# BHOnOfreDevBoard.net
KiCad netlist of a schematic drawn in EAGLE
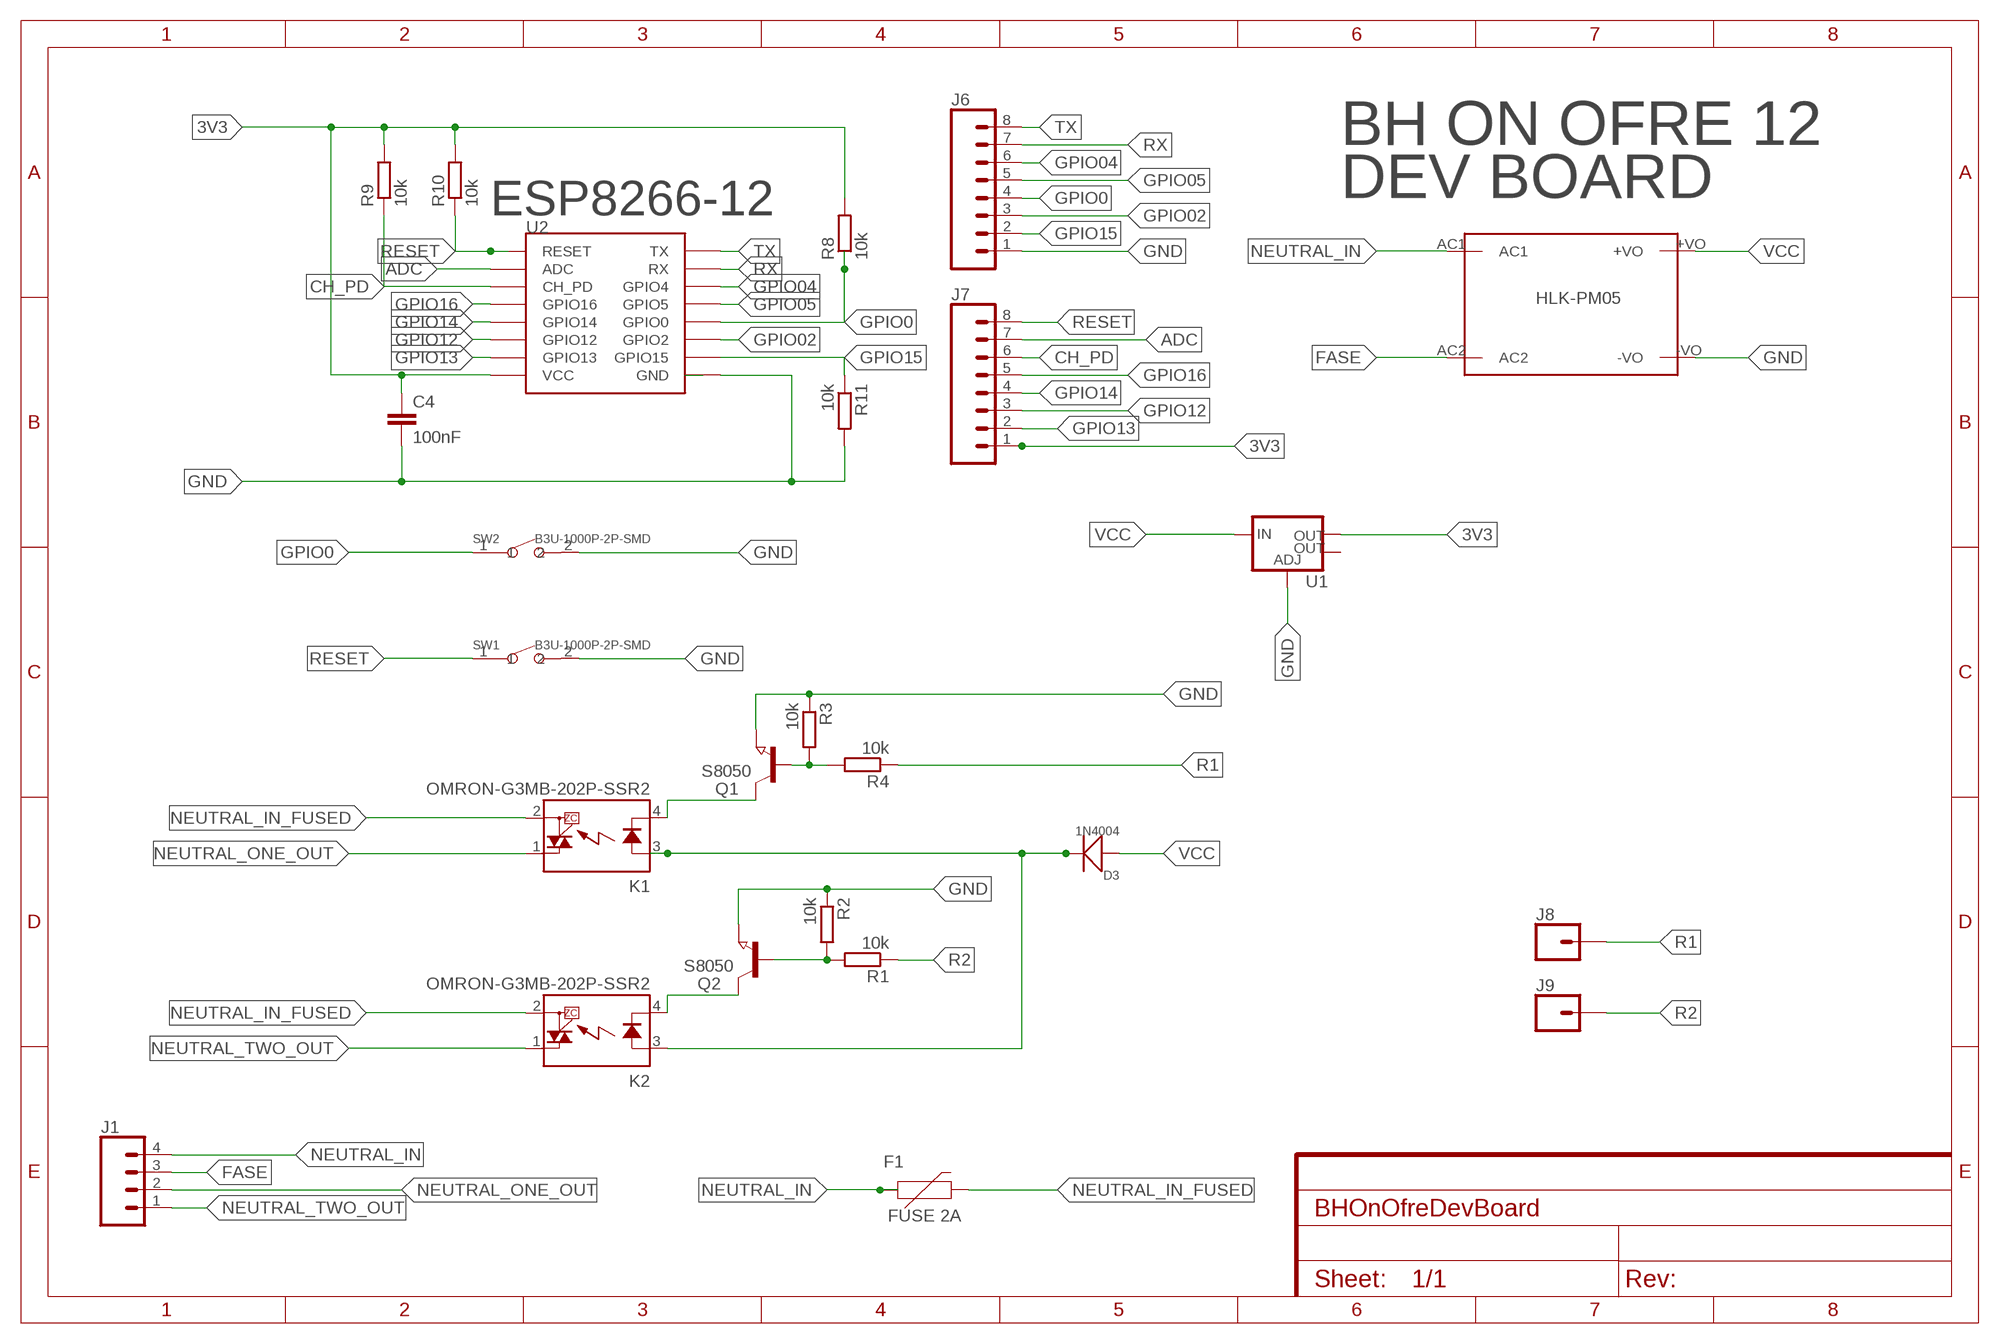
[diagram p0: schematic, sheet 1]

(export (version "E")
  (design (tool "Eeschema 10.0.6"))
  (components
    (comp (ref "C4")
      (value "100nF")
      (footprint "eagle-import:0603")
      (libsource (lib "eagle-import") (part "10NF-0603-50V-10%"))
    )
    (comp (ref "D3")
      (value "1N4004")
      (footprint "eagle-import:DO-214AC")
      (fields (field (name "MPN") "1N4007"))
      (libsource (lib "eagle-import") (part "DIODE-GEN-PURPOSE-1KV-1A(DO-214AC)"))
    )
    (comp (ref "F1")
      (value "FUSE 2A")
      (footprint "eagle-import:PTH")
      (libsource (lib "eagle-import") (part "PPTC_PTH"))
    )
    (comp (ref "J1")
      (value "CONN_04SCREW")
      (footprint "eagle-import:SCREWTERMINAL-3.5MM-4")
      (libsource (lib "eagle-import") (part "CONN_04SCREW"))
    )
    (comp (ref "J6")
      (value "CONN_08\"")
      (footprint "eagle-import:1X08")
      (libsource (lib "eagle-import") (part "CONN_08{dblquote}"))
    )
    (comp (ref "J7")
      (value "CONN_08\"")
      (footprint "eagle-import:1X08")
      (libsource (lib "eagle-import") (part "CONN_08{dblquote}"))
    )
    (comp (ref "J8")
      (value "CONN_01")
      (footprint "eagle-import:1X01")
      (libsource (lib "eagle-import") (part "CONN_01"))
    )
    (comp (ref "J9")
      (value "CONN_01")
      (footprint "eagle-import:1X01")
      (libsource (lib "eagle-import") (part "CONN_01"))
    )
    (comp (ref "K1")
      (value "OMRON-G3MB-202P-SSR2")
      (footprint "eagle-import:OMRON-G3MB-202P-SSR")
      (fields (field (name "MPN") "S202S02F"))
      (libsource (lib "eagle-import") (part "OMRON-G3MB-202P-SSR2"))
    )
    (comp (ref "K2")
      (value "OMRON-G3MB-202P-SSR2")
      (footprint "eagle-import:OMRON-G3MB-202P-SSR")
      (fields (field (name "MPN") "S202S02F"))
      (libsource (lib "eagle-import") (part "OMRON-G3MB-202P-SSR2"))
    )
    (comp (ref "Q1")
      (value "S8050")
      (footprint "eagle-import:SOT23")
      (libsource (lib "eagle-import") (part "NPN-TRANSISTOR_SOT23"))
    )
    (comp (ref "Q2")
      (value "S8050")
      (footprint "eagle-import:SOT23")
      (libsource (lib "eagle-import") (part "NPN-TRANSISTOR_SOT23"))
    )
    (comp (ref "R1")
      (value "10k")
      (footprint "eagle-import:R0603")
      (libsource (lib "eagle-import") (part "R-EU_R0603"))
    )
    (comp (ref "R2")
      (value "10k")
      (footprint "eagle-import:R0603")
      (libsource (lib "eagle-import") (part "R-EU_R0603"))
    )
    (comp (ref "R3")
      (value "10k")
      (footprint "eagle-import:R0603")
      (libsource (lib "eagle-import") (part "R-EU_R0603"))
    )
    (comp (ref "R4")
      (value "10k")
      (footprint "eagle-import:R0603")
      (libsource (lib "eagle-import") (part "R-EU_R0603"))
    )
    (comp (ref "R8")
      (value "10k")
      (footprint "eagle-import:R0603")
      (libsource (lib "eagle-import") (part "R-EU_R0603"))
    )
    (comp (ref "R9")
      (value "10k")
      (footprint "eagle-import:R0603")
      (libsource (lib "eagle-import") (part "R-EU_R0603"))
    )
    (comp (ref "R10")
      (value "10k")
      (footprint "eagle-import:R0603")
      (libsource (lib "eagle-import") (part "R-EU_R0603"))
    )
    (comp (ref "R11")
      (value "10k")
      (footprint "eagle-import:R0603")
      (libsource (lib "eagle-import") (part "R-EU_R0603"))
    )
    (comp (ref "SW1")
      (value "B3U-1000P-2P-SMD")
      (footprint "eagle-import:SW2-2.6-3.0X2.5X1.2+0.4MM")
      (libsource (lib "eagle-import") (part "SMD-BUTTON(2P-3.0X2.5X1.2+0.4MM)-B3U-1000P-2P-SMD"))
    )
    (comp (ref "SW2")
      (value "B3U-1000P-2P-SMD")
      (footprint "eagle-import:SW2-2.6-3.0X2.5X1.2+0.4MM")
      (libsource (lib "eagle-import") (part "SMD-BUTTON(2P-3.0X2.5X1.2+0.4MM)-B3U-1000P-2P-SMD"))
    )
    (comp (ref "U$2")
      (value "HLK-PM03")
      (footprint "eagle-import:HLK-PM03")
      (libsource (lib "eagle-import") (part "HLK-PM03"))
    )
    (comp (ref "U1")
      (value "V_REG_LM1117SOT223")
      (footprint "eagle-import:SOT223")
      (libsource (lib "eagle-import") (part "V_REG_LM1117SOT223"))
    )
    (comp (ref "U2")
      (value "ESP12SMD")
      (footprint "eagle-import:ESP12-SMD")
      (libsource (lib "eagle-import") (part "ESP12SMD"))
    )
  )
  (nets
    (net (code "1") (name "3V3") (class "Default")
      (node (ref "C4") (pin "1") (pinfunction "1_1") (pintype "passive"))
      (node (ref "J7") (pin "1") (pinfunction "1_1") (pintype "passive"))
      (node (ref "R10") (pin "2") (pinfunction "2_2") (pintype "passive"))
      (node (ref "R8") (pin "2") (pinfunction "2_2") (pintype "passive"))
      (node (ref "R9") (pin "2") (pinfunction "2_2") (pintype "passive"))
      (node (ref "U1") (pin "2") (pinfunction "OUT_2") (pintype "output"))
      (node (ref "U2") (pin "VCC") (pinfunction "VCC_VCC") (pintype "bidirectional"))
    )
    (net (code "2") (name "ADC") (class "Default")
      (node (ref "J7") (pin "7") (pinfunction "7_7") (pintype "passive"))
      (node (ref "U2") (pin "ADC") (pinfunction "ADC_ADC") (pintype "bidirectional"))
    )
    (net (code "3") (name "CH_PD") (class "Default")
      (node (ref "J7") (pin "6") (pinfunction "6_6") (pintype "passive"))
      (node (ref "R9") (pin "1") (pinfunction "1_1") (pintype "passive"))
      (node (ref "U2") (pin "CH_PD") (pinfunction "CH_PD_CH_PD") (pintype "bidirectional"))
    )
    (net (code "4") (name "FASE") (class "Default")
      (node (ref "J1") (pin "3") (pinfunction "3_3") (pintype "passive"))
      (node (ref "U$2") (pin "AC2") (pinfunction "AC2_AC2") (pintype "bidirectional"))
    )
    (net (code "5") (name "GND") (class "Default")
      (node (ref "C4") (pin "2") (pinfunction "2_2") (pintype "passive"))
      (node (ref "J6") (pin "1") (pinfunction "1_1") (pintype "passive"))
      (node (ref "Q1") (pin "2") (pinfunction "E_2") (pintype "passive"))
      (node (ref "Q2") (pin "2") (pinfunction "E_2") (pintype "passive"))
      (node (ref "R11") (pin "2") (pinfunction "2_2") (pintype "passive"))
      (node (ref "R2") (pin "1") (pinfunction "1_1") (pintype "passive"))
      (node (ref "R3") (pin "1") (pinfunction "1_1") (pintype "passive"))
      (node (ref "SW1") (pin "2") (pinfunction "2_2") (pintype "bidirectional"))
      (node (ref "SW2") (pin "2") (pinfunction "2_2") (pintype "bidirectional"))
      (node (ref "U$2") (pin "-VO") (pinfunction "-VO_-VO") (pintype "bidirectional"))
      (node (ref "U1") (pin "1") (pinfunction "ADJ_1") (pintype "input"))
      (node (ref "U2") (pin "GND") (pinfunction "GND_GND") (pintype "bidirectional"))
    )
    (net (code "6") (name "GPIO0") (class "Default")
      (node (ref "J6") (pin "4") (pinfunction "4_4") (pintype "passive"))
      (node (ref "R8") (pin "1") (pinfunction "1_1") (pintype "passive"))
      (node (ref "SW2") (pin "1") (pinfunction "1_1") (pintype "bidirectional"))
      (node (ref "U2") (pin "GPIO0") (pinfunction "GPIO0_GPIO0") (pintype "bidirectional"))
    )
    (net (code "7") (name "GPIO02") (class "Default")
      (node (ref "J6") (pin "3") (pinfunction "3_3") (pintype "passive"))
      (node (ref "U2") (pin "GPIO2") (pinfunction "GPIO2_GPIO2") (pintype "bidirectional"))
    )
    (net (code "8") (name "GPIO04") (class "Default")
      (node (ref "J6") (pin "6") (pinfunction "6_6") (pintype "passive"))
      (node (ref "U2") (pin "GPIO4") (pinfunction "GPIO4_GPIO4") (pintype "bidirectional"))
    )
    (net (code "9") (name "GPIO05") (class "Default")
      (node (ref "J6") (pin "5") (pinfunction "5_5") (pintype "passive"))
      (node (ref "U2") (pin "GPIO5") (pinfunction "GPIO5_GPIO5") (pintype "bidirectional"))
    )
    (net (code "10") (name "GPIO12") (class "Default")
      (node (ref "J7") (pin "3") (pinfunction "3_3") (pintype "passive"))
      (node (ref "U2") (pin "GPIO12") (pinfunction "GPIO12_GPIO12") (pintype "bidirectional"))
    )
    (net (code "11") (name "GPIO13") (class "Default")
      (node (ref "J7") (pin "2") (pinfunction "2_2") (pintype "passive"))
      (node (ref "U2") (pin "GPIO13") (pinfunction "GPIO13_GPIO13") (pintype "bidirectional"))
    )
    (net (code "12") (name "GPIO14") (class "Default")
      (node (ref "J7") (pin "4") (pinfunction "4_4") (pintype "passive"))
      (node (ref "U2") (pin "GPIO14") (pinfunction "GPIO14_GPIO14") (pintype "bidirectional"))
    )
    (net (code "13") (name "GPIO15") (class "Default")
      (node (ref "J6") (pin "2") (pinfunction "2_2") (pintype "passive"))
      (node (ref "R11") (pin "1") (pinfunction "1_1") (pintype "passive"))
      (node (ref "U2") (pin "GPIO15") (pinfunction "GPIO15_GPIO15") (pintype "bidirectional"))
    )
    (net (code "14") (name "GPIO16") (class "Default")
      (node (ref "J7") (pin "5") (pinfunction "5_5") (pintype "passive"))
      (node (ref "U2") (pin "GPIO16") (pinfunction "GPIO16_GPIO16") (pintype "bidirectional"))
    )
    (net (code "15") (name "NEUTRAL_IN") (class "Default")
      (node (ref "F1") (pin "P$1") (pinfunction "1_P$1") (pintype "bidirectional"))
      (node (ref "J1") (pin "4") (pinfunction "4_4") (pintype "passive"))
      (node (ref "U$2") (pin "AC1") (pinfunction "AC1_AC1") (pintype "bidirectional"))
    )
    (net (code "16") (name "NEUTRAL_IN_FUSED") (class "Default")
      (node (ref "F1") (pin "P$2") (pinfunction "2_P$2") (pintype "bidirectional"))
      (node (ref "K1") (pin "2") (pinfunction "DS2_2") (pintype "passive"))
      (node (ref "K2") (pin "2") (pinfunction "DS2_2") (pintype "passive"))
    )
    (net (code "17") (name "NEUTRAL_ONE_OUT") (class "Default")
      (node (ref "J1") (pin "2") (pinfunction "2_2") (pintype "passive"))
      (node (ref "K1") (pin "1") (pinfunction "DS1_1") (pintype "passive"))
    )
    (net (code "18") (name "NEUTRAL_TWO_OUT") (class "Default")
      (node (ref "J1") (pin "1") (pinfunction "1_1") (pintype "passive"))
      (node (ref "K2") (pin "1") (pinfunction "DS1_1") (pintype "passive"))
    )
    (net (code "19") (name "Net-(D3--)") (class "Default")
      (node (ref "D3") (pin "2") (pinfunction "-_2") (pintype "passive"))
      (node (ref "K1") (pin "3") (pinfunction "A_3") (pintype "passive"))
      (node (ref "K2") (pin "3") (pinfunction "A_3") (pintype "passive"))
    )
    (net (code "20") (name "Net-(K1-K)") (class "Default")
      (node (ref "K1") (pin "4") (pinfunction "K_4") (pintype "passive"))
      (node (ref "Q1") (pin "3") (pinfunction "C_3") (pintype "passive"))
    )
    (net (code "21") (name "Net-(K2-K)") (class "Default")
      (node (ref "K2") (pin "4") (pinfunction "K_4") (pintype "passive"))
      (node (ref "Q2") (pin "3") (pinfunction "C_3") (pintype "passive"))
    )
    (net (code "22") (name "Net-(Q1-B)") (class "Default")
      (node (ref "Q1") (pin "1") (pinfunction "B_1") (pintype "passive"))
      (node (ref "R3") (pin "2") (pinfunction "2_2") (pintype "passive"))
      (node (ref "R4") (pin "2") (pinfunction "2_2") (pintype "passive"))
    )
    (net (code "23") (name "Net-(Q2-B)") (class "Default")
      (node (ref "Q2") (pin "1") (pinfunction "B_1") (pintype "passive"))
      (node (ref "R1") (pin "2") (pinfunction "2_2") (pintype "passive"))
      (node (ref "R2") (pin "2") (pinfunction "2_2") (pintype "passive"))
    )
    (net (code "24") (name "R1") (class "Default")
      (node (ref "J8") (pin "1") (pinfunction "1_1") (pintype "passive"))
      (node (ref "R4") (pin "1") (pinfunction "1_1") (pintype "passive"))
    )
    (net (code "25") (name "R2") (class "Default")
      (node (ref "J9") (pin "1") (pinfunction "1_1") (pintype "passive"))
      (node (ref "R1") (pin "1") (pinfunction "1_1") (pintype "passive"))
    )
    (net (code "26") (name "RESET") (class "Default")
      (node (ref "J7") (pin "8") (pinfunction "8_8") (pintype "passive"))
      (node (ref "R10") (pin "1") (pinfunction "1_1") (pintype "passive"))
      (node (ref "SW1") (pin "1") (pinfunction "1_1") (pintype "bidirectional"))
      (node (ref "U2") (pin "RESET") (pinfunction "RESET_RESET") (pintype "bidirectional"))
    )
    (net (code "27") (name "RX") (class "Default")
      (node (ref "J6") (pin "7") (pinfunction "7_7") (pintype "passive"))
      (node (ref "U2") (pin "RXD0") (pinfunction "RX_RXD0") (pintype "bidirectional"))
    )
    (net (code "28") (name "TX") (class "Default")
      (node (ref "J6") (pin "8") (pinfunction "8_8") (pintype "passive"))
      (node (ref "U2") (pin "TXD0") (pinfunction "TX_TXD0") (pintype "bidirectional"))
    )
    (net (code "29") (name "VCC") (class "Default")
      (node (ref "D3") (pin "1") (pinfunction "+_1") (pintype "passive"))
      (node (ref "U$2") (pin "+VO") (pinfunction "+VO_+VO") (pintype "bidirectional"))
      (node (ref "U1") (pin "3") (pinfunction "IN_3") (pintype "input"))
    )
    (net (code "30") (name "unconnected-(U1-OUT-Pad4)") (class "Default")
      (node (ref "U1") (pin "4") (pinfunction "OUT_4") (pintype "output"))
    )
  )
)
